# astronaut_interface.net
KiCad netlist of a schematic drawn in EAGLE
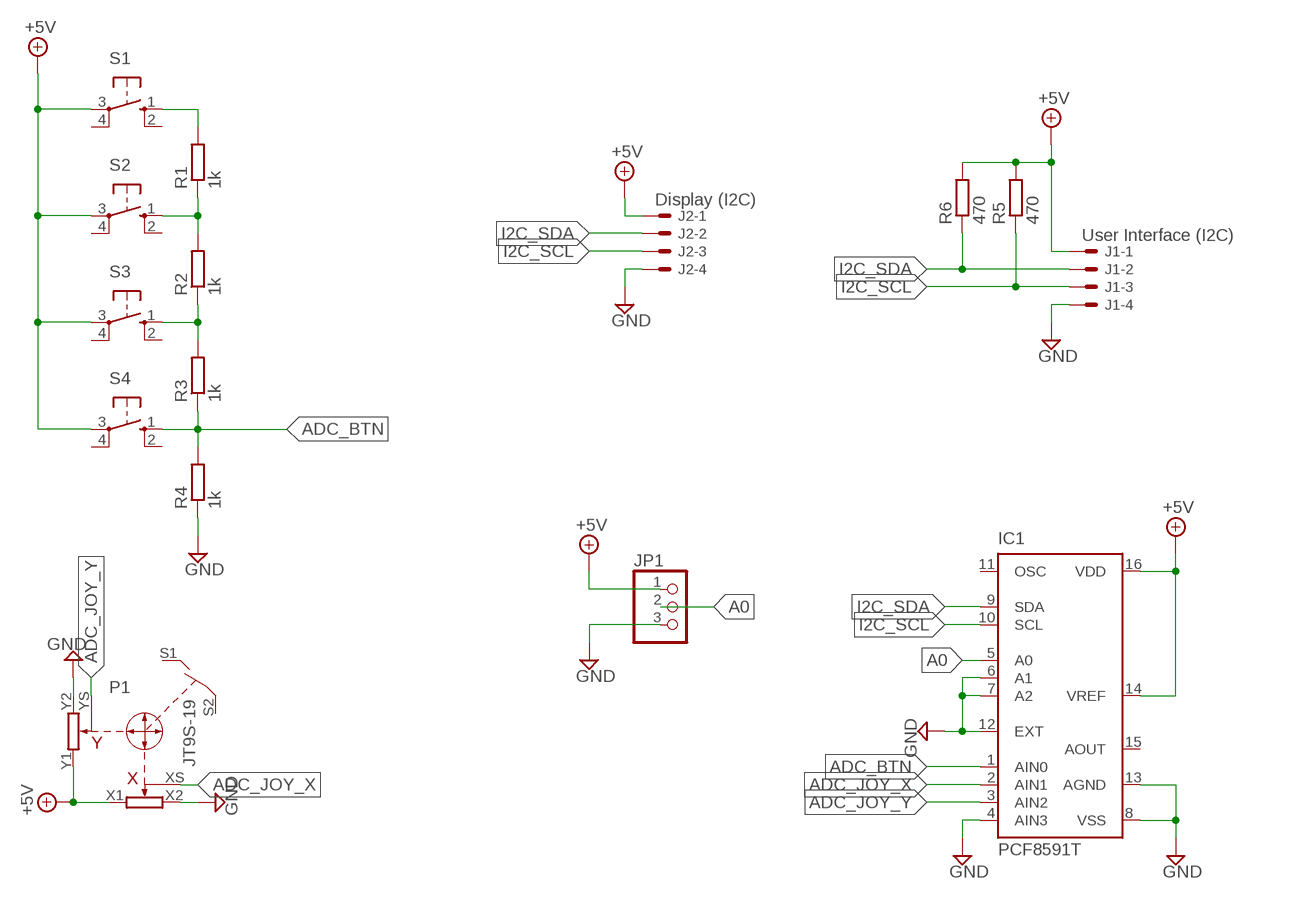
[diagram p0: schematic, sheet 1]

(export (version "E")
  (design (tool "Eeschema 10.0.6"))
  (components
    (comp (ref "IC1")
      (value "PCF8591T")
      (footprint "eagle-import:SO16W")
      (fields (field (name "MPN") "PCF8591T/2,512"))
      (libsource (lib "eagle-import") (part "PCF8591T"))
    )
    (comp (ref "J1")
      (value "User Interface (I2C)")
      (footprint "eagle-import:7395-04")
      (libsource (lib "eagle-import") (part "22-?-0405-7048"))
    )
    (comp (ref "J2")
      (value "Display (I2C)")
      (footprint "eagle-import:7395-04")
      (libsource (lib "eagle-import") (part "22-?-0405-7048"))
    )
    (comp (ref "JP1")
      (value "PINHD-1X3")
      (footprint "eagle-import:1X03")
      (libsource (lib "eagle-import") (part "PINHD-1X3"))
    )
    (comp (ref "P1")
      (value "JT9S-19")
      (footprint "eagle-import:JT9S-1P")
      (libsource (lib "eagle-import") (part "JT9S-19"))
    )
    (comp (ref "R1")
      (value "1k")
      (footprint "eagle-import:R0805")
      (libsource (lib "eagle-import") (part "R-EU_R0805"))
    )
    (comp (ref "R2")
      (value "1k")
      (footprint "eagle-import:R0805")
      (libsource (lib "eagle-import") (part "R-EU_R0805"))
    )
    (comp (ref "R3")
      (value "1k")
      (footprint "eagle-import:R0805")
      (libsource (lib "eagle-import") (part "R-EU_R0805"))
    )
    (comp (ref "R4")
      (value "1k")
      (footprint "eagle-import:R0805")
      (libsource (lib "eagle-import") (part "R-EU_R0805"))
    )
    (comp (ref "R5")
      (value "470")
      (footprint "eagle-import:M0805")
      (libsource (lib "eagle-import") (part "resistor_R-EU_M0805"))
    )
    (comp (ref "R6")
      (value "470")
      (footprint "eagle-import:M0805")
      (libsource (lib "eagle-import") (part "resistor_R-EU_M0805"))
    )
    (comp (ref "S1")
      (value "10-XX")
      (footprint "eagle-import:B3F-10XX")
      (fields (field (name "MPN") "B3F-1000"))
      (libsource (lib "eagle-import") (part "10-XX"))
    )
    (comp (ref "S2")
      (value "10-XX")
      (footprint "eagle-import:B3F-10XX")
      (fields (field (name "MPN") "B3F-1000"))
      (libsource (lib "eagle-import") (part "10-XX"))
    )
    (comp (ref "S3")
      (value "10-XX")
      (footprint "eagle-import:B3F-10XX")
      (fields (field (name "MPN") "B3F-1000"))
      (libsource (lib "eagle-import") (part "10-XX"))
    )
    (comp (ref "S4")
      (value "10-XX")
      (footprint "eagle-import:B3F-10XX")
      (fields (field (name "MPN") "B3F-1000"))
      (libsource (lib "eagle-import") (part "10-XX"))
    )
  )
  (nets
    (net (code "1") (name "+5V") (class "Default")
      (node (ref "IC1") (pin "14") (pinfunction "VREF_14") (pintype "input"))
      (node (ref "IC1") (pin "16") (pinfunction "VDD_16") (pintype "power_in"))
      (node (ref "J1") (pin "1") (pinfunction "S_1") (pintype "passive"))
      (node (ref "J2") (pin "1") (pinfunction "S_1") (pintype "passive"))
      (node (ref "JP1") (pin "1") (pinfunction "1_1") (pintype "passive"))
      (node (ref "P1") (pin "X1") (pinfunction "X1_X1") (pintype "passive"))
      (node (ref "P1") (pin "Y1") (pinfunction "Y1_Y1") (pintype "passive"))
      (node (ref "R5") (pin "2") (pinfunction "2_2") (pintype "passive"))
      (node (ref "R6") (pin "2") (pinfunction "2_2") (pintype "passive"))
      (node (ref "S1") (pin "3") (pinfunction "P_3") (pintype "passive"))
      (node (ref "S2") (pin "3") (pinfunction "P_3") (pintype "passive"))
      (node (ref "S3") (pin "3") (pinfunction "P_3") (pintype "passive"))
      (node (ref "S4") (pin "3") (pinfunction "P_3") (pintype "passive"))
    )
    (net (code "2") (name "A0") (class "Default")
      (node (ref "IC1") (pin "5") (pinfunction "A0_5") (pintype "input"))
      (node (ref "JP1") (pin "2") (pinfunction "2_2") (pintype "passive"))
    )
    (net (code "3") (name "ADC_BTN") (class "Default")
      (node (ref "IC1") (pin "1") (pinfunction "AIN0_1") (pintype "input"))
      (node (ref "R3") (pin "1") (pinfunction "1_1") (pintype "passive"))
      (node (ref "R4") (pin "2") (pinfunction "2_2") (pintype "passive"))
      (node (ref "S4") (pin "1") (pinfunction "S_1") (pintype "passive"))
    )
    (net (code "4") (name "ADC_JOY_X") (class "Default")
      (node (ref "IC1") (pin "2") (pinfunction "AIN1_2") (pintype "input"))
      (node (ref "P1") (pin "XS") (pinfunction "XS_XS") (pintype "passive"))
    )
    (net (code "5") (name "ADC_JOY_Y") (class "Default")
      (node (ref "IC1") (pin "3") (pinfunction "AIN2_3") (pintype "input"))
      (node (ref "P1") (pin "YS") (pinfunction "YS_YS") (pintype "passive"))
    )
    (net (code "6") (name "GND") (class "Default")
      (node (ref "IC1") (pin "12") (pinfunction "EXT_12") (pintype "input"))
      (node (ref "IC1") (pin "13") (pinfunction "AGND_13") (pintype "power_in"))
      (node (ref "IC1") (pin "4") (pinfunction "AIN3_4") (pintype "input"))
      (node (ref "IC1") (pin "6") (pinfunction "A1_6") (pintype "input"))
      (node (ref "IC1") (pin "7") (pinfunction "A2_7") (pintype "input"))
      (node (ref "IC1") (pin "8") (pinfunction "VSS_8") (pintype "power_in"))
      (node (ref "J1") (pin "4") (pinfunction "S_4") (pintype "passive"))
      (node (ref "J2") (pin "4") (pinfunction "S_4") (pintype "passive"))
      (node (ref "JP1") (pin "3") (pinfunction "3_3") (pintype "passive"))
      (node (ref "P1") (pin "X2") (pinfunction "X2_X2") (pintype "passive"))
      (node (ref "P1") (pin "Y2") (pinfunction "Y2_Y2") (pintype "passive"))
      (node (ref "R4") (pin "1") (pinfunction "1_1") (pintype "passive"))
    )
    (net (code "7") (name "I2C_SCL") (class "Default")
      (node (ref "IC1") (pin "10") (pinfunction "SCL_10") (pintype "input"))
      (node (ref "J1") (pin "3") (pinfunction "S_3") (pintype "passive"))
      (node (ref "J2") (pin "3") (pinfunction "S_3") (pintype "passive"))
      (node (ref "R5") (pin "1") (pinfunction "1_1") (pintype "passive"))
    )
    (net (code "8") (name "I2C_SDA") (class "Default")
      (node (ref "IC1") (pin "9") (pinfunction "SDA_9") (pintype "bidirectional"))
      (node (ref "J1") (pin "2") (pinfunction "S_2") (pintype "passive"))
      (node (ref "J2") (pin "2") (pinfunction "S_2") (pintype "passive"))
      (node (ref "R6") (pin "1") (pinfunction "1_1") (pintype "passive"))
    )
    (net (code "9") (name "Net-(S1-S)") (class "Default")
      (node (ref "R1") (pin "2") (pinfunction "2_2") (pintype "passive"))
      (node (ref "S1") (pin "1") (pinfunction "S_1") (pintype "passive"))
    )
    (net (code "10") (name "Net-(S2-S)") (class "Default")
      (node (ref "R1") (pin "1") (pinfunction "1_1") (pintype "passive"))
      (node (ref "R2") (pin "2") (pinfunction "2_2") (pintype "passive"))
      (node (ref "S2") (pin "1") (pinfunction "S_1") (pintype "passive"))
    )
    (net (code "11") (name "Net-(S3-S)") (class "Default")
      (node (ref "R2") (pin "1") (pinfunction "1_1") (pintype "passive"))
      (node (ref "R3") (pin "2") (pinfunction "2_2") (pintype "passive"))
      (node (ref "S3") (pin "1") (pinfunction "S_1") (pintype "passive"))
    )
    (net (code "12") (name "unconnected-(IC1-AOUT-Pad15)") (class "Default")
      (node (ref "IC1") (pin "15") (pinfunction "AOUT_15") (pintype "output"))
    )
    (net (code "13") (name "unconnected-(IC1-OSC-Pad11)") (class "Default")
      (node (ref "IC1") (pin "11") (pinfunction "OSC_11") (pintype "input"))
    )
    (net (code "14") (name "unconnected-(P1-PadS1)") (class "Default")
      (node (ref "P1") (pin "S1") (pinfunction "S1_S1") (pintype "passive"))
    )
    (net (code "15") (name "unconnected-(P1-PadS2)") (class "Default")
      (node (ref "P1") (pin "S2") (pinfunction "S2_S2") (pintype "passive"))
    )
    (net (code "16") (name "unconnected-(S1-P1-Pad4)") (class "Default")
      (node (ref "S1") (pin "4") (pinfunction "P1_4") (pintype "passive"))
    )
    (net (code "17") (name "unconnected-(S1-S1-Pad2)") (class "Default")
      (node (ref "S1") (pin "2") (pinfunction "S1_2") (pintype "passive"))
    )
    (net (code "18") (name "unconnected-(S2-P1-Pad4)") (class "Default")
      (node (ref "S2") (pin "4") (pinfunction "P1_4") (pintype "passive"))
    )
    (net (code "19") (name "unconnected-(S2-S1-Pad2)") (class "Default")
      (node (ref "S2") (pin "2") (pinfunction "S1_2") (pintype "passive"))
    )
    (net (code "20") (name "unconnected-(S3-P1-Pad4)") (class "Default")
      (node (ref "S3") (pin "4") (pinfunction "P1_4") (pintype "passive"))
    )
    (net (code "21") (name "unconnected-(S3-S1-Pad2)") (class "Default")
      (node (ref "S3") (pin "2") (pinfunction "S1_2") (pintype "passive"))
    )
    (net (code "22") (name "unconnected-(S4-P1-Pad4)") (class "Default")
      (node (ref "S4") (pin "4") (pinfunction "P1_4") (pintype "passive"))
    )
    (net (code "23") (name "unconnected-(S4-S1-Pad2)") (class "Default")
      (node (ref "S4") (pin "2") (pinfunction "S1_2") (pintype "passive"))
    )
  )
)
